# Codeshelf-0004_v02.net
KiCad netlist of a schematic drawn in EAGLE
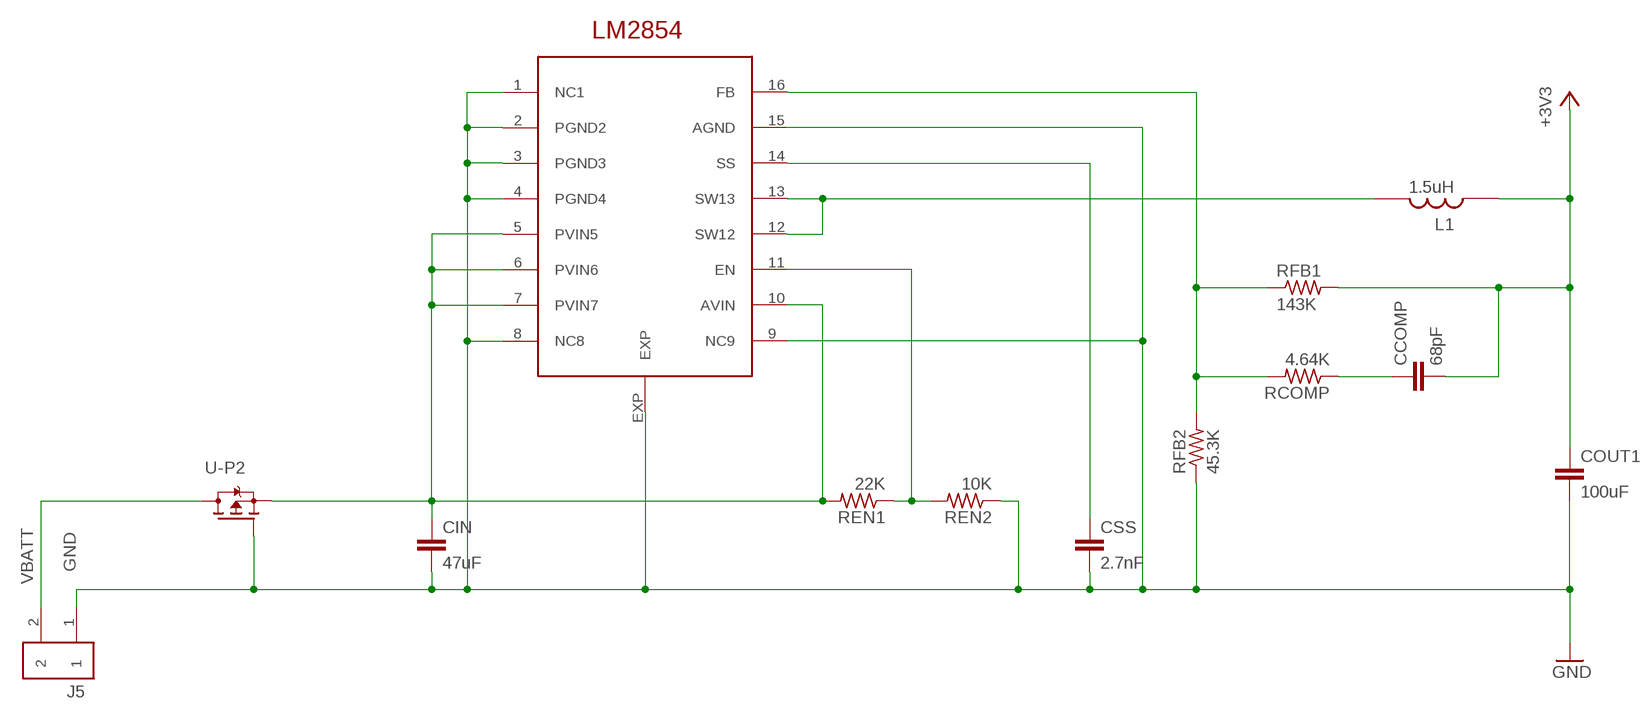
[diagram p0: schematic, sheet 1]

(export (version "E")
  (design (tool "Eeschema 10.0.6"))
  (components
    (comp (ref "CCOMP")
      (value "68pF")
      (footprint "eagle-import:C0805")
      (libsource (lib "eagle-import") (part "RF-C0805"))
    )
    (comp (ref "CIN")
      (value "47uF")
      (footprint "eagle-import:C1210K")
      (libsource (lib "eagle-import") (part "RF-C1210"))
    )
    (comp (ref "COUT1")
      (value "100uF")
      (footprint "eagle-import:C1210K")
      (libsource (lib "eagle-import") (part "RF-C1210"))
    )
    (comp (ref "CSS")
      (value "2.7nF")
      (footprint "eagle-import:C0805")
      (libsource (lib "eagle-import") (part "RF-C0805"))
    )
    (comp (ref "J5")
      (value "HEADER-2X-2.54MM")
      (footprint "eagle-import:HEADER-2X-RA-2.54MM")
      (libsource (lib "eagle-import") (part "HEADER-2X-2.54MM"))
    )
    (comp (ref "L1")
      (value "1.5uH")
      (footprint "eagle-import:SLF10165")
      (libsource (lib "eagle-import") (part "INDUCTOR-SMD-UNUSUAL-SLF10165"))
    )
    (comp (ref "RCOMP")
      (value "4.64K")
      (footprint "eagle-import:RF-R0402")
      (libsource (lib "eagle-import") (part "RF-R0402"))
    )
    (comp (ref "REN1")
      (value "22K")
      (footprint "eagle-import:RF-R0402")
      (libsource (lib "eagle-import") (part "RF-R0402"))
    )
    (comp (ref "REN2")
      (value "10K")
      (footprint "eagle-import:RF-R0402")
      (libsource (lib "eagle-import") (part "RF-R0402"))
    )
    (comp (ref "RFB1")
      (value "143K")
      (footprint "eagle-import:RF-R0402")
      (libsource (lib "eagle-import") (part "RF-R0402"))
    )
    (comp (ref "RFB2")
      (value "45.3K")
      (footprint "eagle-import:RF-R0402")
      (libsource (lib "eagle-import") (part "RF-R0402"))
    )
    (comp (ref "U-P1")
      (value "LM2854MH")
      (footprint "eagle-import:HTSSOP16PWP")
      (libsource (lib "eagle-import") (part "LM2854MH"))
    )
    (comp (ref "U-P2")
      (value "PCHANNEL-MOSFET-DPAK")
      (footprint "eagle-import:DPAK")
      (libsource (lib "eagle-import") (part "PCHANNEL-MOSFET-DPAK"))
    )
  )
  (nets
    (net (code "1") (name "+3V3") (class "Default")
      (node (ref "CCOMP") (pin "2") (pinfunction "2_2") (pintype "passive"))
      (node (ref "COUT1") (pin "1") (pinfunction "1_1") (pintype "passive"))
      (node (ref "L1") (pin "2") (pinfunction "2_2") (pintype "bidirectional"))
      (node (ref "RFB1") (pin "2") (pinfunction "2_2") (pintype "passive"))
    )
    (net (code "2") (name "/VBATT") (class "Default")
      (node (ref "J5") (pin "2") (pinfunction "2_2") (pintype "bidirectional"))
      (node (ref "U-P2") (pin "4") (pinfunction "D_4") (pintype "passive"))
    )
    (net (code "3") (name "GND") (class "Default")
      (node (ref "CIN") (pin "2") (pinfunction "2_2") (pintype "passive"))
      (node (ref "COUT1") (pin "2") (pinfunction "2_2") (pintype "passive"))
      (node (ref "CSS") (pin "2") (pinfunction "2_2") (pintype "passive"))
      (node (ref "J5") (pin "1") (pinfunction "1_1") (pintype "bidirectional"))
      (node (ref "REN2") (pin "1") (pinfunction "1_1") (pintype "passive"))
      (node (ref "RFB2") (pin "1") (pinfunction "1_1") (pintype "passive"))
      (node (ref "U-P1") (pin "1") (pinfunction "NC1_1") (pintype "bidirectional"))
      (node (ref "U-P1") (pin "15") (pinfunction "AGND_15") (pintype "bidirectional"))
      (node (ref "U-P1") (pin "2") (pinfunction "PGND2_2") (pintype "bidirectional"))
      (node (ref "U-P1") (pin "3") (pinfunction "PGND3_3") (pintype "bidirectional"))
      (node (ref "U-P1") (pin "4") (pinfunction "PGND4_4") (pintype "bidirectional"))
      (node (ref "U-P1") (pin "8") (pinfunction "NC8_8") (pintype "bidirectional"))
      (node (ref "U-P1") (pin "9") (pinfunction "NC9_9") (pintype "bidirectional"))
      (node (ref "U-P1") (pin "EXP") (pinfunction "EXP_EXP") (pintype "bidirectional"))
      (node (ref "U-P2") (pin "1") (pinfunction "G_1") (pintype "passive"))
    )
    (net (code "4") (name "Net-(CCOMP-Pad1)") (class "Default")
      (node (ref "CCOMP") (pin "1") (pinfunction "1_1") (pintype "passive"))
      (node (ref "RCOMP") (pin "1") (pinfunction "1_1") (pintype "passive"))
    )
    (net (code "5") (name "Net-(U-P1-AVIN)") (class "Default")
      (node (ref "CIN") (pin "1") (pinfunction "1_1") (pintype "passive"))
      (node (ref "REN1") (pin "2") (pinfunction "2_2") (pintype "passive"))
      (node (ref "U-P1") (pin "10") (pinfunction "AVIN_10") (pintype "bidirectional"))
      (node (ref "U-P1") (pin "5") (pinfunction "PVIN5_5") (pintype "bidirectional"))
      (node (ref "U-P1") (pin "6") (pinfunction "PVIN6_6") (pintype "bidirectional"))
      (node (ref "U-P1") (pin "7") (pinfunction "PVIN7_7") (pintype "bidirectional"))
      (node (ref "U-P2") (pin "3") (pinfunction "S_3") (pintype "passive"))
    )
    (net (code "6") (name "Net-(U-P1-EN)") (class "Default")
      (node (ref "REN1") (pin "1") (pinfunction "1_1") (pintype "passive"))
      (node (ref "REN2") (pin "2") (pinfunction "2_2") (pintype "passive"))
      (node (ref "U-P1") (pin "11") (pinfunction "EN_11") (pintype "bidirectional"))
    )
    (net (code "7") (name "Net-(U-P1-FB)") (class "Default")
      (node (ref "RCOMP") (pin "2") (pinfunction "2_2") (pintype "passive"))
      (node (ref "RFB1") (pin "1") (pinfunction "1_1") (pintype "passive"))
      (node (ref "RFB2") (pin "2") (pinfunction "2_2") (pintype "passive"))
      (node (ref "U-P1") (pin "16") (pinfunction "FB_16") (pintype "bidirectional"))
    )
    (net (code "8") (name "Net-(U-P1-SS)") (class "Default")
      (node (ref "CSS") (pin "1") (pinfunction "1_1") (pintype "passive"))
      (node (ref "U-P1") (pin "14") (pinfunction "SS_14") (pintype "bidirectional"))
    )
    (net (code "9") (name "Net-(U-P1-SW12)") (class "Default")
      (node (ref "L1") (pin "1") (pinfunction "1_1") (pintype "bidirectional"))
      (node (ref "U-P1") (pin "12") (pinfunction "SW12_12") (pintype "bidirectional"))
      (node (ref "U-P1") (pin "13") (pinfunction "SW13_13") (pintype "bidirectional"))
    )
  )
)
